# Eagle_BluetoothProtoboardAdapter.net
KiCad netlist of a schematic drawn in EAGLE
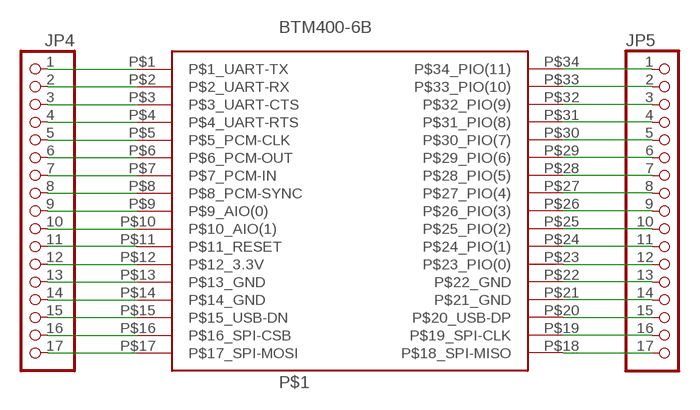
[diagram p0: schematic, sheet 1]

(export (version "E")
  (design (tool "Eeschema 10.0.6"))
  (components
    (comp (ref "JP4")
      (value "PINHD-1X17")
      (footprint "eagle-import:1X17")
      (libsource (lib "eagle-import") (part "PINHD-1X17"))
    )
    (comp (ref "JP5")
      (value "PINHD-1X17")
      (footprint "eagle-import:1X17")
      (libsource (lib "eagle-import") (part "PINHD-1X17"))
    )
    (comp (ref "P$1")
      (value "BTM400-6B")
      (footprint "eagle-import:BTM400")
      (libsource (lib "eagle-import") (part "BTM400-6B"))
    )
  )
  (nets
    (net (code "1") (name "Net-(P$1-P$1_UART-TX)") (class "Default")
      (node (ref "JP4") (pin "1") (pinfunction "1_1") (pintype "passive"))
      (node (ref "P$1") (pin "P$1") (pinfunction "P$1_UART-TX_P$1") (pintype "output"))
    )
    (net (code "2") (name "Net-(P$1-P$2_UART-RX)") (class "Default")
      (node (ref "JP4") (pin "2") (pinfunction "2_2") (pintype "passive"))
      (node (ref "P$1") (pin "P$2") (pinfunction "P$2_UART-RX_P$2") (pintype "input"))
    )
    (net (code "3") (name "Net-(P$1-P$3_UART-CTS)") (class "Default")
      (node (ref "JP4") (pin "3") (pinfunction "3_3") (pintype "passive"))
      (node (ref "P$1") (pin "P$3") (pinfunction "P$3_UART-CTS_P$3") (pintype "input"))
    )
    (net (code "4") (name "Net-(P$1-P$4_UART-RTS)") (class "Default")
      (node (ref "JP4") (pin "4") (pinfunction "4_4") (pintype "passive"))
      (node (ref "P$1") (pin "P$4") (pinfunction "P$4_UART-RTS_P$4") (pintype "output"))
    )
    (net (code "5") (name "Net-(P$1-P$5_PCM-CLK)") (class "Default")
      (node (ref "JP4") (pin "5") (pinfunction "5_5") (pintype "passive"))
      (node (ref "P$1") (pin "P$5") (pinfunction "P$5_PCM-CLK_P$5") (pintype "bidirectional"))
    )
    (net (code "6") (name "Net-(P$1-P$6_PCM-OUT)") (class "Default")
      (node (ref "JP4") (pin "6") (pinfunction "6_6") (pintype "passive"))
      (node (ref "P$1") (pin "P$6") (pinfunction "P$6_PCM-OUT_P$6") (pintype "output"))
    )
    (net (code "7") (name "Net-(P$1-P$7_PCM-IN)") (class "Default")
      (node (ref "JP4") (pin "7") (pinfunction "7_7") (pintype "passive"))
      (node (ref "P$1") (pin "P$7") (pinfunction "P$7_PCM-IN_P$7") (pintype "input"))
    )
    (net (code "8") (name "Net-(P$1-P$8_PCM-SYNC)") (class "Default")
      (node (ref "JP4") (pin "8") (pinfunction "8_8") (pintype "passive"))
      (node (ref "P$1") (pin "P$8") (pinfunction "P$8_PCM-SYNC_P$8") (pintype "bidirectional"))
    )
    (net (code "9") (name "Net-(P$1-P$9_AIO(0))") (class "Default")
      (node (ref "JP4") (pin "9") (pinfunction "9_9") (pintype "passive"))
      (node (ref "P$1") (pin "P$9") (pinfunction "P$9_AIO(0)_P$9") (pintype "bidirectional"))
    )
    (net (code "10") (name "Net-(P$1-P$10_AIO(1))") (class "Default")
      (node (ref "JP4") (pin "10") (pinfunction "10_10") (pintype "passive"))
      (node (ref "P$1") (pin "P$10") (pinfunction "P$10_AIO(1)_P$10") (pintype "bidirectional"))
    )
    (net (code "11") (name "Net-(P$1-P$11_RESET)") (class "Default")
      (node (ref "JP4") (pin "11") (pinfunction "11_11") (pintype "passive"))
      (node (ref "P$1") (pin "P$11") (pinfunction "P$11_RESET_P$11") (pintype "input"))
    )
    (net (code "12") (name "Net-(P$1-P$12_3.3V)") (class "Default")
      (node (ref "JP4") (pin "12") (pinfunction "12_12") (pintype "passive"))
      (node (ref "P$1") (pin "P$12") (pinfunction "P$12_3.3V_P$12") (pintype "power_in"))
    )
    (net (code "13") (name "Net-(P$1-P$13_GND)") (class "Default")
      (node (ref "JP4") (pin "13") (pinfunction "13_13") (pintype "passive"))
      (node (ref "P$1") (pin "P$13") (pinfunction "P$13_GND_P$13") (pintype "power_in"))
    )
    (net (code "14") (name "Net-(P$1-P$14_GND)") (class "Default")
      (node (ref "JP4") (pin "14") (pinfunction "14_14") (pintype "passive"))
      (node (ref "P$1") (pin "P$14") (pinfunction "P$14_GND_P$14") (pintype "power_in"))
    )
    (net (code "15") (name "Net-(P$1-P$15_USB-DN)") (class "Default")
      (node (ref "JP4") (pin "15") (pinfunction "15_15") (pintype "passive"))
      (node (ref "P$1") (pin "P$15") (pinfunction "P$15_USB-DN_P$15") (pintype "bidirectional"))
    )
    (net (code "16") (name "Net-(P$1-P$16_SPI-CSB)") (class "Default")
      (node (ref "JP4") (pin "16") (pinfunction "16_16") (pintype "passive"))
      (node (ref "P$1") (pin "P$16") (pinfunction "P$16_SPI-CSB_P$16") (pintype "input"))
    )
    (net (code "17") (name "Net-(P$1-P$17_SPI-MOSI)") (class "Default")
      (node (ref "JP4") (pin "17") (pinfunction "17_17") (pintype "passive"))
      (node (ref "P$1") (pin "P$17") (pinfunction "P$17_SPI-MOSI_P$17") (pintype "input"))
    )
    (net (code "18") (name "Net-(P$1-P$18_SPI-MISO)") (class "Default")
      (node (ref "JP5") (pin "17") (pinfunction "17_17") (pintype "passive"))
      (node (ref "P$1") (pin "P$18") (pinfunction "P$18_SPI-MISO_P$18") (pintype "output"))
    )
    (net (code "19") (name "Net-(P$1-P$19_SPI-CLK)") (class "Default")
      (node (ref "JP5") (pin "16") (pinfunction "16_16") (pintype "passive"))
      (node (ref "P$1") (pin "P$19") (pinfunction "P$19_SPI-CLK_P$19") (pintype "input"))
    )
    (net (code "20") (name "Net-(P$1-P$20_USB-DP)") (class "Default")
      (node (ref "JP5") (pin "15") (pinfunction "15_15") (pintype "passive"))
      (node (ref "P$1") (pin "P$20") (pinfunction "P$20_USB-DP_P$20") (pintype "bidirectional"))
    )
    (net (code "21") (name "Net-(P$1-P$21_GND)") (class "Default")
      (node (ref "JP5") (pin "14") (pinfunction "14_14") (pintype "passive"))
      (node (ref "P$1") (pin "P$21") (pinfunction "P$21_GND_P$21") (pintype "power_in"))
    )
    (net (code "22") (name "Net-(P$1-P$22_GND)") (class "Default")
      (node (ref "JP5") (pin "13") (pinfunction "13_13") (pintype "passive"))
      (node (ref "P$1") (pin "P$22") (pinfunction "P$22_GND_P$22") (pintype "power_in"))
    )
    (net (code "23") (name "Net-(P$1-P$23_PIO(0))") (class "Default")
      (node (ref "JP5") (pin "12") (pinfunction "12_12") (pintype "passive"))
      (node (ref "P$1") (pin "P$23") (pinfunction "P$23_PIO(0)_P$23") (pintype "bidirectional"))
    )
    (net (code "24") (name "Net-(P$1-P$24_PIO(1))") (class "Default")
      (node (ref "JP5") (pin "11") (pinfunction "11_11") (pintype "passive"))
      (node (ref "P$1") (pin "P$24") (pinfunction "P$24_PIO(1)_P$24") (pintype "bidirectional"))
    )
    (net (code "25") (name "Net-(P$1-P$25_PIO(2))") (class "Default")
      (node (ref "JP5") (pin "10") (pinfunction "10_10") (pintype "passive"))
      (node (ref "P$1") (pin "P$25") (pinfunction "P$25_PIO(2)_P$25") (pintype "bidirectional"))
    )
    (net (code "26") (name "Net-(P$1-P$26_PIO(3))") (class "Default")
      (node (ref "JP5") (pin "9") (pinfunction "9_9") (pintype "passive"))
      (node (ref "P$1") (pin "P$26") (pinfunction "P$26_PIO(3)_P$26") (pintype "bidirectional"))
    )
    (net (code "27") (name "Net-(P$1-P$27_PIO(4))") (class "Default")
      (node (ref "JP5") (pin "8") (pinfunction "8_8") (pintype "passive"))
      (node (ref "P$1") (pin "P$27") (pinfunction "P$27_PIO(4)_P$27") (pintype "bidirectional"))
    )
    (net (code "28") (name "Net-(P$1-P$28_PIO(5))") (class "Default")
      (node (ref "JP5") (pin "7") (pinfunction "7_7") (pintype "passive"))
      (node (ref "P$1") (pin "P$28") (pinfunction "P$28_PIO(5)_P$28") (pintype "bidirectional"))
    )
    (net (code "29") (name "Net-(P$1-P$29_PIO(6))") (class "Default")
      (node (ref "JP5") (pin "6") (pinfunction "6_6") (pintype "passive"))
      (node (ref "P$1") (pin "P$29") (pinfunction "P$29_PIO(6)_P$29") (pintype "bidirectional"))
    )
    (net (code "30") (name "Net-(P$1-P$30_PIO(7))") (class "Default")
      (node (ref "JP5") (pin "5") (pinfunction "5_5") (pintype "passive"))
      (node (ref "P$1") (pin "P$30") (pinfunction "P$30_PIO(7)_P$30") (pintype "bidirectional"))
    )
    (net (code "31") (name "Net-(P$1-P$31_PIO(8))") (class "Default")
      (node (ref "JP5") (pin "4") (pinfunction "4_4") (pintype "passive"))
      (node (ref "P$1") (pin "P$31") (pinfunction "P$31_PIO(8)_P$31") (pintype "bidirectional"))
    )
    (net (code "32") (name "Net-(P$1-P$32_PIO(9))") (class "Default")
      (node (ref "JP5") (pin "3") (pinfunction "3_3") (pintype "passive"))
      (node (ref "P$1") (pin "P$32") (pinfunction "P$32_PIO(9)_P$32") (pintype "bidirectional"))
    )
    (net (code "33") (name "Net-(P$1-P$33_PIO(10))") (class "Default")
      (node (ref "JP5") (pin "2") (pinfunction "2_2") (pintype "passive"))
      (node (ref "P$1") (pin "P$33") (pinfunction "P$33_PIO(10)_P$33") (pintype "bidirectional"))
    )
    (net (code "34") (name "Net-(P$1-P$34_PIO(11))") (class "Default")
      (node (ref "JP5") (pin "1") (pinfunction "1_1") (pintype "passive"))
      (node (ref "P$1") (pin "P$34") (pinfunction "P$34_PIO(11)_P$34") (pintype "bidirectional"))
    )
  )
)
